# ZynqPL.net
KiCad netlist of a schematic drawn in Altium Designer
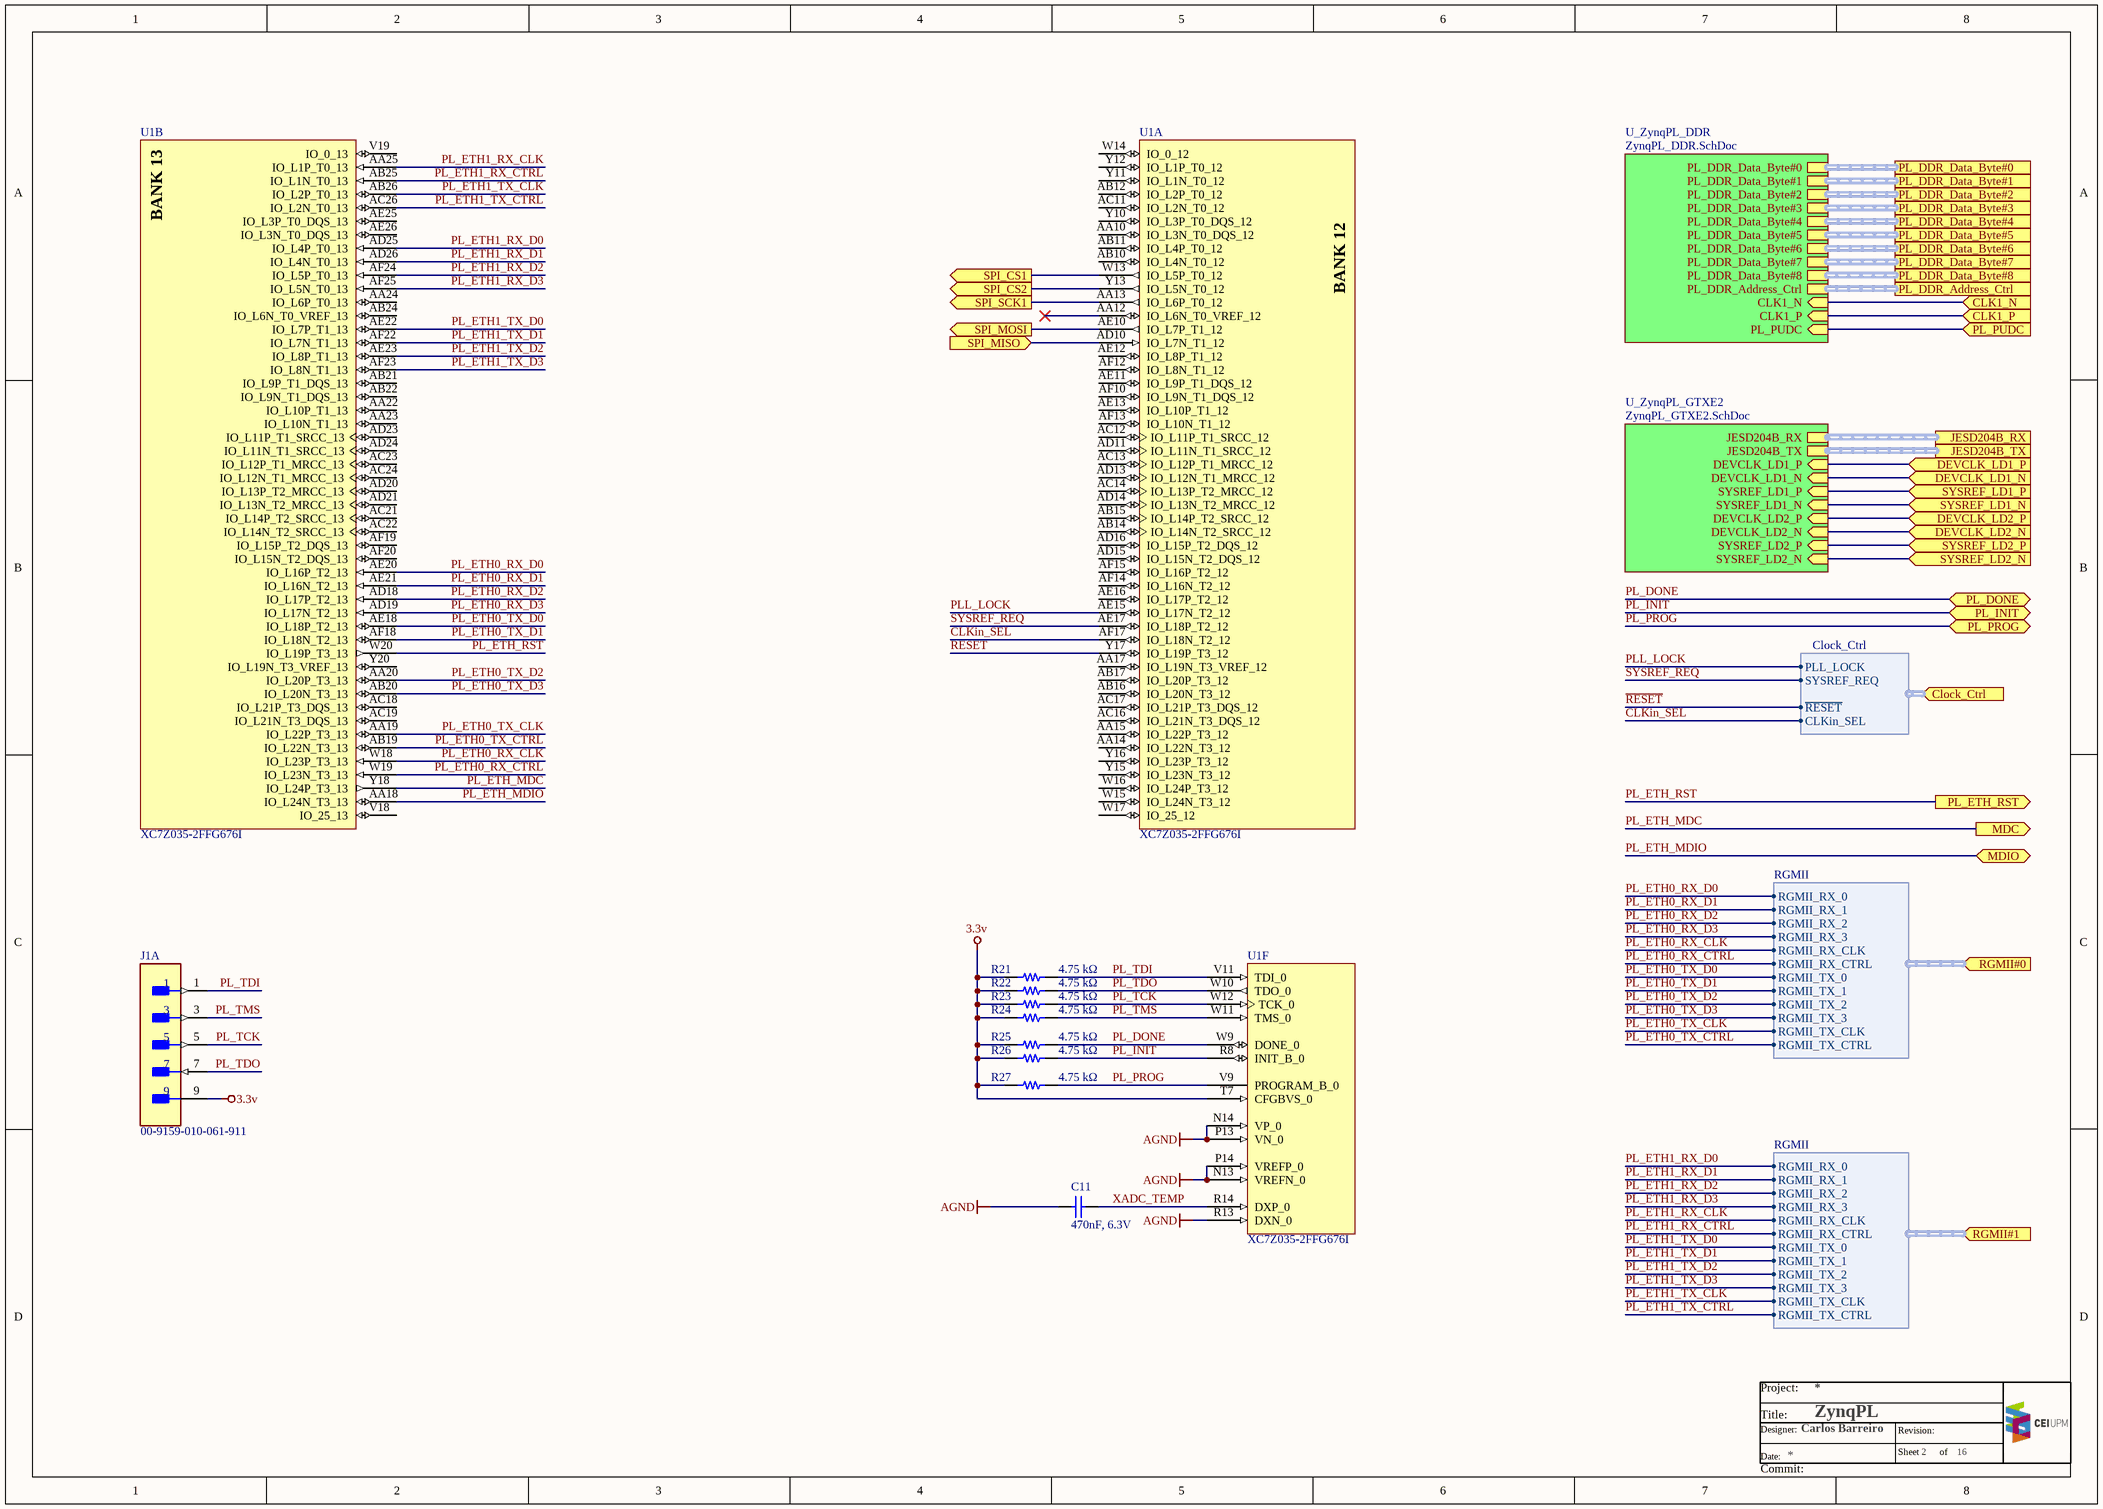
[diagram p0: ZynqPL.SchDoc]

(export (version "E")
  (design (tool "Eeschema 10.0.6"))
  (components
    (comp (ref "C11")
      (value "470nF, 6.3V")
      (footprint "WURTH_WCAP-CSGP_0402")
      (description "WCAP-CSGP Multilayer Ceramic Chip Capacitor, General Purpose, size 0402, X5R, 470nF, 6.3V")
      (fields
        (field (name "MANUFACTURER PART NUMBER") "885012105004")
        (field (name "MANUFACTURER") "Wurth Elektronik")
      )
      (libsource (lib "SpaceVNXBaseBoard") (part "885012105004"))
    )
    (comp (ref "J1")
      (value "00-9159-010-061-911")
      (footprint "KYOCERA_00-9159-010-061-911")
      (description "Coplanar Open Ended Card Edge Connector 10 Pin")
      (libsource (lib "SpaceVNXBaseBoard") (part "00-9159-010-061-911"))
    )
    (comp (ref "R21")
      (value "4.75 kΩ")
      (footprint "PANASONIC_ERJ2G_0402")
      (description "General Purpose Thick Film Chip Resistors")
      (fields (field (name "MANUFACTURER") "Panasonic"))
      (libsource (lib "SpaceVNXBaseBoard") (part "ERJ2RKF4751X"))
    )
    (comp (ref "R22")
      (value "4.75 kΩ")
      (footprint "PANASONIC_ERJ2G_0402")
      (description "General Purpose Thick Film Chip Resistors")
      (fields (field (name "MANUFACTURER") "Panasonic"))
      (libsource (lib "SpaceVNXBaseBoard") (part "ERJ2RKF4751X"))
    )
    (comp (ref "R23")
      (value "4.75 kΩ")
      (footprint "PANASONIC_ERJ2G_0402")
      (description "General Purpose Thick Film Chip Resistors")
      (fields (field (name "MANUFACTURER") "Panasonic"))
      (libsource (lib "SpaceVNXBaseBoard") (part "ERJ2RKF4751X"))
    )
    (comp (ref "R24")
      (value "4.75 kΩ")
      (footprint "PANASONIC_ERJ2G_0402")
      (description "General Purpose Thick Film Chip Resistors")
      (fields (field (name "MANUFACTURER") "Panasonic"))
      (libsource (lib "SpaceVNXBaseBoard") (part "ERJ2RKF4751X"))
    )
    (comp (ref "R25")
      (value "4.75 kΩ")
      (footprint "PANASONIC_ERJ2G_0402")
      (description "General Purpose Thick Film Chip Resistors")
      (fields (field (name "MANUFACTURER") "Panasonic"))
      (libsource (lib "SpaceVNXBaseBoard") (part "ERJ2RKF4751X"))
    )
    (comp (ref "R26")
      (value "4.75 kΩ")
      (footprint "PANASONIC_ERJ2G_0402")
      (description "General Purpose Thick Film Chip Resistors")
      (fields (field (name "MANUFACTURER") "Panasonic"))
      (libsource (lib "SpaceVNXBaseBoard") (part "ERJ2RKF4751X"))
    )
    (comp (ref "R27")
      (value "4.75 kΩ")
      (footprint "PANASONIC_ERJ2G_0402")
      (description "General Purpose Thick Film Chip Resistors")
      (fields (field (name "MANUFACTURER") "Panasonic"))
      (libsource (lib "SpaceVNXBaseBoard") (part "ERJ2RKF4751X"))
    )
    (comp (ref "U1")
      (value "XC7Z035-2FFG676I")
      (footprint "XILINX_FBG676")
      (fields (field (name "PARTNUMBER") "XC7Z035-2FBG676I") (field (name "GENERIC PART NUMBER") "XC7Z035"))
      (libsource (lib "SpaceVNXBaseBoard") (part "XC7Z035-2FFG676I"))
    )
  )
  (nets
    (net (code "17") (name "/CLKin_SEL") (class "Default")
      (node (ref "U1") (pin "AF17") (pinfunction "IO_L18N_T2_12_AF17") (pintype "bidirectional"))
    )
    (net (code "24") (name "/PLL_LOCK") (class "Default")
      (node (ref "U1") (pin "AE15") (pinfunction "IO_L17N_T2_12_AE15") (pintype "bidirectional"))
    )
    (net (code "35") (name "/PL_DONE") (class "Default")
      (node (ref "R25") (pin "2") (pinfunction "2_2") (pintype "passive"))
      (node (ref "U1") (pin "W9") (pinfunction "DONE_0_W9") (pintype "bidirectional"))
    )
    (net (code "36") (name "/PL_ETH0_RX_CLK") (class "Default")
      (node (ref "U1") (pin "W18") (pinfunction "IO_L23P_T3_13_W18") (pintype "input"))
    )
    (net (code "37") (name "/PL_ETH0_RX_CTRL") (class "Default")
      (node (ref "U1") (pin "W19") (pinfunction "IO_L23N_T3_13_W19") (pintype "input"))
    )
    (net (code "38") (name "/PL_ETH0_RX_D0") (class "Default")
      (node (ref "U1") (pin "AE20") (pinfunction "IO_L16P_T2_13_AE20") (pintype "input"))
    )
    (net (code "39") (name "/PL_ETH0_RX_D1") (class "Default")
      (node (ref "U1") (pin "AE21") (pinfunction "IO_L16N_T2_13_AE21") (pintype "input"))
    )
    (net (code "40") (name "/PL_ETH0_RX_D2") (class "Default")
      (node (ref "U1") (pin "AD18") (pinfunction "IO_L17P_T2_13_AD18") (pintype "input"))
    )
    (net (code "41") (name "/PL_ETH0_RX_D3") (class "Default")
      (node (ref "U1") (pin "AD19") (pinfunction "IO_L17N_T2_13_AD19") (pintype "input"))
    )
    (net (code "42") (name "/PL_ETH0_TX_CLK") (class "Default")
      (node (ref "U1") (pin "AA19") (pinfunction "IO_L22P_T3_13_AA19") (pintype "bidirectional"))
    )
    (net (code "43") (name "/PL_ETH0_TX_CTRL") (class "Default")
      (node (ref "U1") (pin "AB19") (pinfunction "IO_L22N_T3_13_AB19") (pintype "bidirectional"))
    )
    (net (code "44") (name "/PL_ETH0_TX_D0") (class "Default")
      (node (ref "U1") (pin "AE18") (pinfunction "IO_L18P_T2_13_AE18") (pintype "bidirectional"))
    )
    (net (code "45") (name "/PL_ETH0_TX_D1") (class "Default")
      (node (ref "U1") (pin "AF18") (pinfunction "IO_L18N_T2_13_AF18") (pintype "bidirectional"))
    )
    (net (code "46") (name "/PL_ETH0_TX_D2") (class "Default")
      (node (ref "U1") (pin "AA20") (pinfunction "IO_L20P_T3_13_AA20") (pintype "bidirectional"))
    )
    (net (code "47") (name "/PL_ETH0_TX_D3") (class "Default")
      (node (ref "U1") (pin "AB20") (pinfunction "IO_L20N_T3_13_AB20") (pintype "bidirectional"))
    )
    (net (code "48") (name "/PL_ETH1_RX_CLK") (class "Default")
      (node (ref "U1") (pin "AA25") (pinfunction "IO_L1P_T0_13_AA25") (pintype "input"))
    )
    (net (code "49") (name "/PL_ETH1_RX_CTRL") (class "Default")
      (node (ref "U1") (pin "AB25") (pinfunction "IO_L1N_T0_13_AB25") (pintype "input"))
    )
    (net (code "50") (name "/PL_ETH1_RX_D0") (class "Default")
      (node (ref "U1") (pin "AD25") (pinfunction "IO_L4P_T0_13_AD25") (pintype "input"))
    )
    (net (code "51") (name "/PL_ETH1_RX_D1") (class "Default")
      (node (ref "U1") (pin "AD26") (pinfunction "IO_L4N_T0_13_AD26") (pintype "input"))
    )
    (net (code "52") (name "/PL_ETH1_RX_D2") (class "Default")
      (node (ref "U1") (pin "AF24") (pinfunction "IO_L5P_T0_13_AF24") (pintype "input"))
    )
    (net (code "53") (name "/PL_ETH1_RX_D3") (class "Default")
      (node (ref "U1") (pin "AF25") (pinfunction "IO_L5N_T0_13_AF25") (pintype "input"))
    )
    (net (code "54") (name "/PL_ETH1_TX_CLK") (class "Default")
      (node (ref "U1") (pin "AB26") (pinfunction "IO_L2P_T0_13_AB26") (pintype "bidirectional"))
    )
    (net (code "55") (name "/PL_ETH1_TX_CTRL") (class "Default")
      (node (ref "U1") (pin "AC26") (pinfunction "IO_L2N_T0_13_AC26") (pintype "bidirectional"))
    )
    (net (code "56") (name "/PL_ETH1_TX_D0") (class "Default")
      (node (ref "U1") (pin "AE22") (pinfunction "IO_L7P_T1_13_AE22") (pintype "bidirectional"))
    )
    (net (code "57") (name "/PL_ETH1_TX_D1") (class "Default")
      (node (ref "U1") (pin "AF22") (pinfunction "IO_L7N_T1_13_AF22") (pintype "bidirectional"))
    )
    (net (code "58") (name "/PL_ETH1_TX_D2") (class "Default")
      (node (ref "U1") (pin "AE23") (pinfunction "IO_L8P_T1_13_AE23") (pintype "bidirectional"))
    )
    (net (code "59") (name "/PL_ETH1_TX_D3") (class "Default")
      (node (ref "U1") (pin "AF23") (pinfunction "IO_L8N_T1_13_AF23") (pintype "bidirectional"))
    )
    (net (code "60") (name "/PL_ETH_MDC") (class "Default")
      (node (ref "U1") (pin "Y18") (pinfunction "IO_L24P_T3_13_Y18") (pintype "output"))
    )
    (net (code "61") (name "/PL_ETH_MDIO") (class "Default")
      (node (ref "U1") (pin "AA18") (pinfunction "IO_L24N_T3_13_AA18") (pintype "bidirectional"))
    )
    (net (code "62") (name "/PL_ETH_RST") (class "Default")
      (node (ref "U1") (pin "W20") (pinfunction "IO_L19P_T3_13_W20") (pintype "output"))
    )
    (net (code "63") (name "/PL_INIT") (class "Default")
      (node (ref "R26") (pin "2") (pinfunction "2_2") (pintype "passive"))
      (node (ref "U1") (pin "R8") (pinfunction "INIT_B_0_R8") (pintype "bidirectional"))
    )
    (net (code "64") (name "/PL_PROG") (class "Default")
      (node (ref "R27") (pin "2") (pinfunction "2_2") (pintype "passive"))
      (node (ref "U1") (pin "V9") (pinfunction "PROGRAM_B_0_V9") (pintype "input"))
    )
    (net (code "66") (name "/PL_TCK") (class "Default")
      (node (ref "J1") (pin "5") (pinfunction "5_5") (pintype "output"))
      (node (ref "R23") (pin "2") (pinfunction "2_2") (pintype "passive"))
      (node (ref "U1") (pin "W12") (pinfunction "TCK_0_W12") (pintype "input"))
    )
    (net (code "67") (name "/PL_TDI") (class "Default")
      (node (ref "J1") (pin "1") (pinfunction "1_1") (pintype "output"))
      (node (ref "R21") (pin "2") (pinfunction "2_2") (pintype "passive"))
      (node (ref "U1") (pin "V11") (pinfunction "TDI_0_V11") (pintype "input"))
    )
    (net (code "68") (name "/PL_TDO") (class "Default")
      (node (ref "J1") (pin "7") (pinfunction "7_7") (pintype "input"))
      (node (ref "R22") (pin "2") (pinfunction "2_2") (pintype "passive"))
      (node (ref "U1") (pin "W10") (pinfunction "TDO_0_W10") (pintype "output"))
    )
    (net (code "69") (name "/PL_TMS") (class "Default")
      (node (ref "J1") (pin "3") (pinfunction "3_3") (pintype "output"))
      (node (ref "R24") (pin "2") (pinfunction "2_2") (pintype "passive"))
      (node (ref "U1") (pin "W11") (pinfunction "TMS_0_W11") (pintype "input"))
    )
    (net (code "70") (name "/SPI_CS1") (class "Default")
      (node (ref "U1") (pin "W13") (pinfunction "IO_L5P_T0_12_W13") (pintype "output"))
    )
    (net (code "71") (name "/SPI_CS2") (class "Default")
      (node (ref "U1") (pin "Y13") (pinfunction "IO_L5N_T0_12_Y13") (pintype "output"))
    )
    (net (code "72") (name "/SPI_MISO") (class "Default")
      (node (ref "U1") (pin "AD10") (pinfunction "IO_L7N_T1_12_AD10") (pintype "input"))
    )
    (net (code "73") (name "/SPI_MOSI") (class "Default")
      (node (ref "U1") (pin "AE10") (pinfunction "IO_L7P_T1_12_AE10") (pintype "output"))
    )
    (net (code "74") (name "/SPI_SCK1") (class "Default")
      (node (ref "U1") (pin "AA13") (pinfunction "IO_L6P_T0_12_AA13") (pintype "output"))
    )
    (net (code "79") (name "/SYSREF_REQ") (class "Default")
      (node (ref "U1") (pin "AE17") (pinfunction "IO_L18P_T2_12_AE17") (pintype "bidirectional"))
    )
    (net (code "80") (name "/XADC_TEMP") (class "Default")
      (node (ref "C11") (pin "2") (pinfunction "2_2") (pintype "passive"))
      (node (ref "U1") (pin "R14") (pinfunction "DXP_0_R14") (pintype "input"))
    )
    (net (code "83") (name "/~{RESET}") (class "Default")
      (node (ref "U1") (pin "Y17") (pinfunction "IO_L19P_T3_12_Y17") (pintype "bidirectional"))
    )
    (net (code "84") (name "3.3v") (class "Default")
      (node (ref "J1") (pin "9") (pinfunction "9_9") (pintype "power_in"))
      (node (ref "R21") (pin "1") (pinfunction "1_1") (pintype "passive"))
      (node (ref "R22") (pin "1") (pinfunction "1_1") (pintype "passive"))
      (node (ref "R23") (pin "1") (pinfunction "1_1") (pintype "passive"))
      (node (ref "R24") (pin "1") (pinfunction "1_1") (pintype "passive"))
      (node (ref "R25") (pin "1") (pinfunction "1_1") (pintype "passive"))
      (node (ref "R26") (pin "1") (pinfunction "1_1") (pintype "passive"))
      (node (ref "R27") (pin "1") (pinfunction "1_1") (pintype "passive"))
      (node (ref "U1") (pin "T7") (pinfunction "CFGBVS_0_T7") (pintype "input"))
    )
    (net (code "85") (name "AGND") (class "Default")
      (node (ref "C11") (pin "1") (pinfunction "1_1") (pintype "passive"))
      (node (ref "U1") (pin "N13") (pinfunction "VREFN_0_N13") (pintype "input"))
      (node (ref "U1") (pin "N14") (pinfunction "VP_0_N14") (pintype "input"))
      (node (ref "U1") (pin "P13") (pinfunction "VN_0_P13") (pintype "input"))
      (node (ref "U1") (pin "P14") (pinfunction "VREFP_0_P14") (pintype "input"))
      (node (ref "U1") (pin "R13") (pinfunction "DXN_0_R13") (pintype "input"))
    )
    (net (code "86") (name "unconnected-(U1A-IO_0_12-PadW14)") (class "Default")
      (node (ref "U1") (pin "W14") (pinfunction "IO_0_12_W14") (pintype "bidirectional"))
    )
    (net (code "87") (name "unconnected-(U1A-IO_25_12-PadW17)") (class "Default")
      (node (ref "U1") (pin "W17") (pinfunction "IO_25_12_W17") (pintype "bidirectional"))
    )
    (net (code "88") (name "unconnected-(U1A-IO_L1N_T0_12-PadY11)") (class "Default")
      (node (ref "U1") (pin "Y11") (pinfunction "IO_L1N_T0_12_Y11") (pintype "bidirectional"))
    )
    (net (code "89") (name "unconnected-(U1A-IO_L1P_T0_12-PadY12)") (class "Default")
      (node (ref "U1") (pin "Y12") (pinfunction "IO_L1P_T0_12_Y12") (pintype "bidirectional"))
    )
    (net (code "90") (name "unconnected-(U1A-IO_L2N_T0_12-PadAC11)") (class "Default")
      (node (ref "U1") (pin "AC11") (pinfunction "IO_L2N_T0_12_AC11") (pintype "bidirectional"))
    )
    (net (code "91") (name "unconnected-(U1A-IO_L2P_T0_12-PadAB12)") (class "Default")
      (node (ref "U1") (pin "AB12") (pinfunction "IO_L2P_T0_12_AB12") (pintype "bidirectional"))
    )
    (net (code "92") (name "unconnected-(U1A-IO_L3N_T0_DQS_12-PadAA10)") (class "Default")
      (node (ref "U1") (pin "AA10") (pinfunction "IO_L3N_T0_DQS_12_AA10") (pintype "bidirectional"))
    )
    (net (code "93") (name "unconnected-(U1A-IO_L3P_T0_DQS_12-PadY10)") (class "Default")
      (node (ref "U1") (pin "Y10") (pinfunction "IO_L3P_T0_DQS_12_Y10") (pintype "bidirectional"))
    )
    (net (code "94") (name "unconnected-(U1A-IO_L4N_T0_12-PadAB10)") (class "Default")
      (node (ref "U1") (pin "AB10") (pinfunction "IO_L4N_T0_12_AB10") (pintype "bidirectional"))
    )
    (net (code "95") (name "unconnected-(U1A-IO_L4P_T0_12-PadAB11)") (class "Default")
      (node (ref "U1") (pin "AB11") (pinfunction "IO_L4P_T0_12_AB11") (pintype "bidirectional"))
    )
    (net (code "96") (name "unconnected-(U1A-IO_L6N_T0_VREF_12-PadAA12)") (class "Default")
      (node (ref "U1") (pin "AA12") (pinfunction "IO_L6N_T0_VREF_12_AA12") (pintype "bidirectional+no_connect"))
    )
    (net (code "97") (name "unconnected-(U1A-IO_L8N_T1_12-PadAF12)") (class "Default")
      (node (ref "U1") (pin "AF12") (pinfunction "IO_L8N_T1_12_AF12") (pintype "bidirectional"))
    )
    (net (code "98") (name "unconnected-(U1A-IO_L8P_T1_12-PadAE12)") (class "Default")
      (node (ref "U1") (pin "AE12") (pinfunction "IO_L8P_T1_12_AE12") (pintype "bidirectional"))
    )
    (net (code "99") (name "unconnected-(U1A-IO_L9N_T1_DQS_12-PadAF10)") (class "Default")
      (node (ref "U1") (pin "AF10") (pinfunction "IO_L9N_T1_DQS_12_AF10") (pintype "bidirectional"))
    )
    (net (code "100") (name "unconnected-(U1A-IO_L9P_T1_DQS_12-PadAE11)") (class "Default")
      (node (ref "U1") (pin "AE11") (pinfunction "IO_L9P_T1_DQS_12_AE11") (pintype "bidirectional"))
    )
    (net (code "101") (name "unconnected-(U1A-IO_L10N_T1_12-PadAF13)") (class "Default")
      (node (ref "U1") (pin "AF13") (pinfunction "IO_L10N_T1_12_AF13") (pintype "bidirectional"))
    )
    (net (code "102") (name "unconnected-(U1A-IO_L10P_T1_12-PadAE13)") (class "Default")
      (node (ref "U1") (pin "AE13") (pinfunction "IO_L10P_T1_12_AE13") (pintype "bidirectional"))
    )
    (net (code "103") (name "unconnected-(U1A-IO_L11N_T1_SRCC_12-PadAD11)") (class "Default")
      (node (ref "U1") (pin "AD11") (pinfunction "IO_L11N_T1_SRCC_12_AD11") (pintype "bidirectional"))
    )
    (net (code "104") (name "unconnected-(U1A-IO_L11P_T1_SRCC_12-PadAC12)") (class "Default")
      (node (ref "U1") (pin "AC12") (pinfunction "IO_L11P_T1_SRCC_12_AC12") (pintype "bidirectional"))
    )
    (net (code "105") (name "unconnected-(U1A-IO_L12N_T1_MRCC_12-PadAD13)") (class "Default")
      (node (ref "U1") (pin "AD13") (pinfunction "IO_L12N_T1_MRCC_12_AD13") (pintype "bidirectional"))
    )
    (net (code "106") (name "unconnected-(U1A-IO_L12P_T1_MRCC_12-PadAC13)") (class "Default")
      (node (ref "U1") (pin "AC13") (pinfunction "IO_L12P_T1_MRCC_12_AC13") (pintype "bidirectional"))
    )
    (net (code "107") (name "unconnected-(U1A-IO_L13N_T2_MRCC_12-PadAD14)") (class "Default")
      (node (ref "U1") (pin "AD14") (pinfunction "IO_L13N_T2_MRCC_12_AD14") (pintype "bidirectional"))
    )
    (net (code "108") (name "unconnected-(U1A-IO_L13P_T2_MRCC_12-PadAC14)") (class "Default")
      (node (ref "U1") (pin "AC14") (pinfunction "IO_L13P_T2_MRCC_12_AC14") (pintype "bidirectional"))
    )
    (net (code "109") (name "unconnected-(U1A-IO_L14N_T2_SRCC_12-PadAB14)") (class "Default")
      (node (ref "U1") (pin "AB14") (pinfunction "IO_L14N_T2_SRCC_12_AB14") (pintype "bidirectional"))
    )
    (net (code "110") (name "unconnected-(U1A-IO_L14P_T2_SRCC_12-PadAB15)") (class "Default")
      (node (ref "U1") (pin "AB15") (pinfunction "IO_L14P_T2_SRCC_12_AB15") (pintype "bidirectional"))
    )
    (net (code "111") (name "unconnected-(U1A-IO_L15N_T2_DQS_12-PadAD15)") (class "Default")
      (node (ref "U1") (pin "AD15") (pinfunction "IO_L15N_T2_DQS_12_AD15") (pintype "bidirectional"))
    )
    (net (code "112") (name "unconnected-(U1A-IO_L15P_T2_DQS_12-PadAD16)") (class "Default")
      (node (ref "U1") (pin "AD16") (pinfunction "IO_L15P_T2_DQS_12_AD16") (pintype "bidirectional"))
    )
    (net (code "113") (name "unconnected-(U1A-IO_L16N_T2_12-PadAF14)") (class "Default")
      (node (ref "U1") (pin "AF14") (pinfunction "IO_L16N_T2_12_AF14") (pintype "bidirectional"))
    )
    (net (code "114") (name "unconnected-(U1A-IO_L16P_T2_12-PadAF15)") (class "Default")
      (node (ref "U1") (pin "AF15") (pinfunction "IO_L16P_T2_12_AF15") (pintype "bidirectional"))
    )
    (net (code "115") (name "unconnected-(U1A-IO_L17P_T2_12-PadAE16)") (class "Default")
      (node (ref "U1") (pin "AE16") (pinfunction "IO_L17P_T2_12_AE16") (pintype "bidirectional"))
    )
    (net (code "116") (name "unconnected-(U1A-IO_L19N_T3_VREF_12-PadAA17)") (class "Default")
      (node (ref "U1") (pin "AA17") (pinfunction "IO_L19N_T3_VREF_12_AA17") (pintype "bidirectional"))
    )
    (net (code "117") (name "unconnected-(U1A-IO_L20N_T3_12-PadAB16)") (class "Default")
      (node (ref "U1") (pin "AB16") (pinfunction "IO_L20N_T3_12_AB16") (pintype "bidirectional"))
    )
    (net (code "118") (name "unconnected-(U1A-IO_L20P_T3_12-PadAB17)") (class "Default")
      (node (ref "U1") (pin "AB17") (pinfunction "IO_L20P_T3_12_AB17") (pintype "bidirectional"))
    )
    (net (code "119") (name "unconnected-(U1A-IO_L21N_T3_DQS_12-PadAC16)") (class "Default")
      (node (ref "U1") (pin "AC16") (pinfunction "IO_L21N_T3_DQS_12_AC16") (pintype "bidirectional"))
    )
    (net (code "120") (name "unconnected-(U1A-IO_L21P_T3_DQS_12-PadAC17)") (class "Default")
      (node (ref "U1") (pin "AC17") (pinfunction "IO_L21P_T3_DQS_12_AC17") (pintype "bidirectional"))
    )
    (net (code "121") (name "unconnected-(U1A-IO_L22N_T3_12-PadAA14)") (class "Default")
      (node (ref "U1") (pin "AA14") (pinfunction "IO_L22N_T3_12_AA14") (pintype "bidirectional"))
    )
    (net (code "122") (name "unconnected-(U1A-IO_L22P_T3_12-PadAA15)") (class "Default")
      (node (ref "U1") (pin "AA15") (pinfunction "IO_L22P_T3_12_AA15") (pintype "bidirectional"))
    )
    (net (code "123") (name "unconnected-(U1A-IO_L23N_T3_12-PadY15)") (class "Default")
      (node (ref "U1") (pin "Y15") (pinfunction "IO_L23N_T3_12_Y15") (pintype "bidirectional"))
    )
    (net (code "124") (name "unconnected-(U1A-IO_L23P_T3_12-PadY16)") (class "Default")
      (node (ref "U1") (pin "Y16") (pinfunction "IO_L23P_T3_12_Y16") (pintype "bidirectional"))
    )
    (net (code "125") (name "unconnected-(U1A-IO_L24N_T3_12-PadW15)") (class "Default")
      (node (ref "U1") (pin "W15") (pinfunction "IO_L24N_T3_12_W15") (pintype "bidirectional"))
    )
    (net (code "126") (name "unconnected-(U1A-IO_L24P_T3_12-PadW16)") (class "Default")
      (node (ref "U1") (pin "W16") (pinfunction "IO_L24P_T3_12_W16") (pintype "bidirectional"))
    )
    (net (code "127") (name "unconnected-(U1B-IO_0_13-PadV19)") (class "Default")
      (node (ref "U1") (pin "V19") (pinfunction "IO_0_13_V19") (pintype "bidirectional"))
    )
    (net (code "128") (name "unconnected-(U1B-IO_25_13-PadV18)") (class "Default")
      (node (ref "U1") (pin "V18") (pinfunction "IO_25_13_V18") (pintype "bidirectional"))
    )
    (net (code "129") (name "unconnected-(U1B-IO_L3N_T0_DQS_13-PadAE26)") (class "Default")
      (node (ref "U1") (pin "AE26") (pinfunction "IO_L3N_T0_DQS_13_AE26") (pintype "bidirectional"))
    )
    (net (code "130") (name "unconnected-(U1B-IO_L3P_T0_DQS_13-PadAE25)") (class "Default")
      (node (ref "U1") (pin "AE25") (pinfunction "IO_L3P_T0_DQS_13_AE25") (pintype "bidirectional"))
    )
    (net (code "131") (name "unconnected-(U1B-IO_L6N_T0_VREF_13-PadAB24)") (class "Default")
      (node (ref "U1") (pin "AB24") (pinfunction "IO_L6N_T0_VREF_13_AB24") (pintype "bidirectional"))
    )
    (net (code "132") (name "unconnected-(U1B-IO_L6P_T0_13-PadAA24)") (class "Default")
      (node (ref "U1") (pin "AA24") (pinfunction "IO_L6P_T0_13_AA24") (pintype "bidirectional"))
    )
    (net (code "133") (name "unconnected-(U1B-IO_L9N_T1_DQS_13-PadAB22)") (class "Default")
      (node (ref "U1") (pin "AB22") (pinfunction "IO_L9N_T1_DQS_13_AB22") (pintype "bidirectional"))
    )
    (net (code "134") (name "unconnected-(U1B-IO_L9P_T1_DQS_13-PadAB21)") (class "Default")
      (node (ref "U1") (pin "AB21") (pinfunction "IO_L9P_T1_DQS_13_AB21") (pintype "bidirectional"))
    )
    (net (code "135") (name "unconnected-(U1B-IO_L10N_T1_13-PadAA23)") (class "Default")
      (node (ref "U1") (pin "AA23") (pinfunction "IO_L10N_T1_13_AA23") (pintype "bidirectional"))
    )
    (net (code "136") (name "unconnected-(U1B-IO_L10P_T1_13-PadAA22)") (class "Default")
      (node (ref "U1") (pin "AA22") (pinfunction "IO_L10P_T1_13_AA22") (pintype "bidirectional"))
    )
    (net (code "137") (name "unconnected-(U1B-IO_L11N_T1_SRCC_13-PadAD24)") (class "Default")
      (node (ref "U1") (pin "AD24") (pinfunction "IO_L11N_T1_SRCC_13_AD24") (pintype "bidirectional"))
    )
    (net (code "138") (name "unconnected-(U1B-IO_L11P_T1_SRCC_13-PadAD23)") (class "Default")
      (node (ref "U1") (pin "AD23") (pinfunction "IO_L11P_T1_SRCC_13_AD23") (pintype "bidirectional"))
    )
    (net (code "139") (name "unconnected-(U1B-IO_L12N_T1_MRCC_13-PadAC24)") (class "Default")
      (node (ref "U1") (pin "AC24") (pinfunction "IO_L12N_T1_MRCC_13_AC24") (pintype "bidirectional"))
    )
    (net (code "140") (name "unconnected-(U1B-IO_L12P_T1_MRCC_13-PadAC23)") (class "Default")
      (node (ref "U1") (pin "AC23") (pinfunction "IO_L12P_T1_MRCC_13_AC23") (pintype "bidirectional"))
    )
    (net (code "141") (name "unconnected-(U1B-IO_L13N_T2_MRCC_13-PadAD21)") (class "Default")
      (node (ref "U1") (pin "AD21") (pinfunction "IO_L13N_T2_MRCC_13_AD21") (pintype "bidirectional"))
    )
    (net (code "142") (name "unconnected-(U1B-IO_L13P_T2_MRCC_13-PadAD20)") (class "Default")
      (node (ref "U1") (pin "AD20") (pinfunction "IO_L13P_T2_MRCC_13_AD20") (pintype "bidirectional"))
    )
    (net (code "143") (name "unconnected-(U1B-IO_L14N_T2_SRCC_13-PadAC22)") (class "Default")
      (node (ref "U1") (pin "AC22") (pinfunction "IO_L14N_T2_SRCC_13_AC22") (pintype "bidirectional"))
    )
    (net (code "144") (name "unconnected-(U1B-IO_L14P_T2_SRCC_13-PadAC21)") (class "Default")
      (node (ref "U1") (pin "AC21") (pinfunction "IO_L14P_T2_SRCC_13_AC21") (pintype "bidirectional"))
    )
    (net (code "145") (name "unconnected-(U1B-IO_L15N_T2_DQS_13-PadAF20)") (class "Default")
      (node (ref "U1") (pin "AF20") (pinfunction "IO_L15N_T2_DQS_13_AF20") (pintype "bidirectional"))
    )
    (net (code "146") (name "unconnected-(U1B-IO_L15P_T2_DQS_13-PadAF19)") (class "Default")
      (node (ref "U1") (pin "AF19") (pinfunction "IO_L15P_T2_DQS_13_AF19") (pintype "bidirectional"))
    )
    (net (code "147") (name "unconnected-(U1B-IO_L19N_T3_VREF_13-PadY20)") (class "Default")
      (node (ref "U1") (pin "Y20") (pinfunction "IO_L19N_T3_VREF_13_Y20") (pintype "bidirectional"))
    )
    (net (code "148") (name "unconnected-(U1B-IO_L21N_T3_DQS_13-PadAC19)") (class "Default")
      (node (ref "U1") (pin "AC19") (pinfunction "IO_L21N_T3_DQS_13_AC19") (pintype "bidirectional"))
    )
    (net (code "149") (name "unconnected-(U1B-IO_L21P_T3_DQS_13-PadAC18)") (class "Default")
      (node (ref "U1") (pin "AC18") (pinfunction "IO_L21P_T3_DQS_13_AC18") (pintype "bidirectional"))
    )
  )
)
